# PinkReq.net
KiCad netlist of a schematic drawn in EAGLE
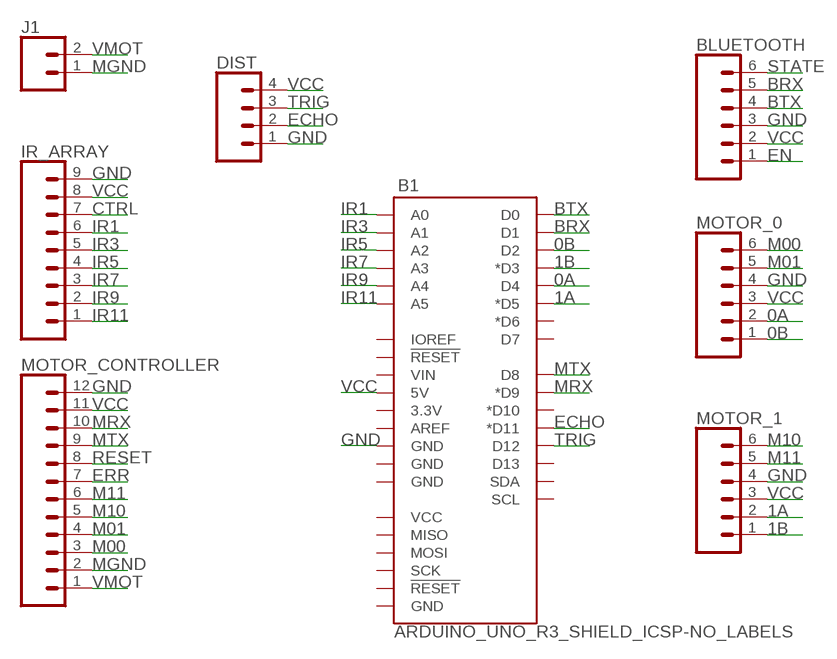
[diagram p0: schematic, sheet 1]

(export (version "E")
  (design (tool "Eeschema 10.0.6"))
  (components
    (comp (ref "B1")
      (value "ARDUINO_UNO_R3_SHIELD_ICSP-NO_LABELS")
      (footprint "eagle-import:UNO_R3_SHIELD_ICSP_NOLABELS")
      (libsource (lib "eagle-import") (part "ARDUINO_UNO_R3_SHIELD_ICSP-NO_LABELS"))
    )
    (comp (ref "BLUETOOTH")
      (value "CONN_06FEMALE_LOCK")
      (footprint "eagle-import:1X06_FEMALE_LOCK.010")
      (libsource (lib "eagle-import") (part "CONN_06FEMALE_LOCK"))
    )
    (comp (ref "DIST")
      (value "CONN_04LOCK")
      (footprint "eagle-import:1X04_LOCK")
      (libsource (lib "eagle-import") (part "CONN_04LOCK"))
    )
    (comp (ref "IR_ARRAY")
      (value "CONN_09LOCK")
      (footprint "eagle-import:1X09_LOCK")
      (libsource (lib "eagle-import") (part "CONN_09LOCK"))
    )
    (comp (ref "J1")
      (value "CONN_025MM")
      (footprint "eagle-import:SCREWTERMINAL-5MM-2")
      (libsource (lib "eagle-import") (part "CONN_025MM"))
    )
    (comp (ref "MOTOR_0")
      (value "CONN_06FEMALE_LOCK")
      (footprint "eagle-import:1X06_FEMALE_LOCK.010")
      (libsource (lib "eagle-import") (part "CONN_06FEMALE_LOCK"))
    )
    (comp (ref "MOTOR_1")
      (value "CONN_06FEMALE_LOCK")
      (footprint "eagle-import:1X06_FEMALE_LOCK.010")
      (libsource (lib "eagle-import") (part "CONN_06FEMALE_LOCK"))
    )
    (comp (ref "MOTOR_CONTROLLER")
      (value "CONN_12LOCK")
      (footprint "eagle-import:1X12_LOCK")
      (libsource (lib "eagle-import") (part "CONN_12LOCK"))
    )
  )
  (nets
    (net (code "1") (name "/0A") (class "Default")
      (node (ref "B1") (pin "D4") (pinfunction "D4_D4") (pintype "bidirectional"))
      (node (ref "MOTOR_0") (pin "2") (pinfunction "2_2") (pintype "passive"))
    )
    (net (code "2") (name "/0B") (class "Default")
      (node (ref "B1") (pin "D2") (pinfunction "D2_D2") (pintype "bidirectional"))
      (node (ref "MOTOR_0") (pin "1") (pinfunction "1_1") (pintype "passive"))
    )
    (net (code "3") (name "/1A") (class "Default")
      (node (ref "B1") (pin "D5") (pinfunction "*D5_D5") (pintype "bidirectional"))
      (node (ref "MOTOR_1") (pin "2") (pinfunction "2_2") (pintype "passive"))
    )
    (net (code "4") (name "/1B") (class "Default")
      (node (ref "B1") (pin "D3") (pinfunction "*D3_D3") (pintype "bidirectional"))
      (node (ref "MOTOR_1") (pin "1") (pinfunction "1_1") (pintype "passive"))
    )
    (net (code "5") (name "/BRX") (class "Default")
      (node (ref "B1") (pin "TX") (pinfunction "D1_TX") (pintype "bidirectional"))
      (node (ref "BLUETOOTH") (pin "5") (pinfunction "5_5") (pintype "passive"))
    )
    (net (code "6") (name "/BTX") (class "Default")
      (node (ref "B1") (pin "RX") (pinfunction "D0_RX") (pintype "bidirectional"))
      (node (ref "BLUETOOTH") (pin "4") (pinfunction "4_4") (pintype "passive"))
    )
    (net (code "7") (name "/CTRL") (class "Default")
      (node (ref "IR_ARRAY") (pin "7") (pinfunction "7_7") (pintype "passive"))
    )
    (net (code "8") (name "/ECHO") (class "Default")
      (node (ref "B1") (pin "D11") (pinfunction "*D11_D11") (pintype "bidirectional"))
      (node (ref "DIST") (pin "2") (pinfunction "2_2") (pintype "passive"))
    )
    (net (code "9") (name "/EN") (class "Default")
      (node (ref "BLUETOOTH") (pin "1") (pinfunction "1_1") (pintype "passive"))
    )
    (net (code "10") (name "/ERR") (class "Default")
      (node (ref "MOTOR_CONTROLLER") (pin "7") (pinfunction "7_7") (pintype "passive"))
    )
    (net (code "11") (name "/GND") (class "Default")
      (node (ref "B1") (pin "GND@2") (pinfunction "GND_GND@2") (pintype "bidirectional"))
      (node (ref "BLUETOOTH") (pin "3") (pinfunction "3_3") (pintype "passive"))
      (node (ref "DIST") (pin "1") (pinfunction "1_1") (pintype "passive"))
      (node (ref "IR_ARRAY") (pin "9") (pinfunction "9_9") (pintype "passive"))
      (node (ref "MOTOR_0") (pin "4") (pinfunction "4_4") (pintype "passive"))
      (node (ref "MOTOR_1") (pin "4") (pinfunction "4_4") (pintype "passive"))
      (node (ref "MOTOR_CONTROLLER") (pin "12") (pinfunction "12_12") (pintype "passive"))
    )
    (net (code "12") (name "/IR1") (class "Default")
      (node (ref "B1") (pin "A0") (pinfunction "A0_A0") (pintype "bidirectional"))
      (node (ref "IR_ARRAY") (pin "6") (pinfunction "6_6") (pintype "passive"))
    )
    (net (code "13") (name "/IR3") (class "Default")
      (node (ref "B1") (pin "A1") (pinfunction "A1_A1") (pintype "bidirectional"))
      (node (ref "IR_ARRAY") (pin "5") (pinfunction "5_5") (pintype "passive"))
    )
    (net (code "14") (name "/IR5") (class "Default")
      (node (ref "B1") (pin "A2") (pinfunction "A2_A2") (pintype "bidirectional"))
      (node (ref "IR_ARRAY") (pin "4") (pinfunction "4_4") (pintype "passive"))
    )
    (net (code "15") (name "/IR7") (class "Default")
      (node (ref "B1") (pin "A3") (pinfunction "A3_A3") (pintype "bidirectional"))
      (node (ref "IR_ARRAY") (pin "3") (pinfunction "3_3") (pintype "passive"))
    )
    (net (code "16") (name "/IR9") (class "Default")
      (node (ref "B1") (pin "A4") (pinfunction "A4_A4") (pintype "bidirectional"))
      (node (ref "IR_ARRAY") (pin "2") (pinfunction "2_2") (pintype "passive"))
    )
    (net (code "17") (name "/IR11") (class "Default")
      (node (ref "B1") (pin "A5") (pinfunction "A5_A5") (pintype "bidirectional"))
      (node (ref "IR_ARRAY") (pin "1") (pinfunction "1_1") (pintype "passive"))
    )
    (net (code "18") (name "/M00") (class "Default")
      (node (ref "MOTOR_0") (pin "6") (pinfunction "6_6") (pintype "passive"))
      (node (ref "MOTOR_CONTROLLER") (pin "3") (pinfunction "3_3") (pintype "passive"))
    )
    (net (code "19") (name "/M01") (class "Default")
      (node (ref "MOTOR_0") (pin "5") (pinfunction "5_5") (pintype "passive"))
      (node (ref "MOTOR_CONTROLLER") (pin "4") (pinfunction "4_4") (pintype "passive"))
    )
    (net (code "20") (name "/M10") (class "Default")
      (node (ref "MOTOR_1") (pin "6") (pinfunction "6_6") (pintype "passive"))
      (node (ref "MOTOR_CONTROLLER") (pin "5") (pinfunction "5_5") (pintype "passive"))
    )
    (net (code "21") (name "/M11") (class "Default")
      (node (ref "MOTOR_1") (pin "5") (pinfunction "5_5") (pintype "passive"))
      (node (ref "MOTOR_CONTROLLER") (pin "6") (pinfunction "6_6") (pintype "passive"))
    )
    (net (code "22") (name "/MGND") (class "Default")
      (node (ref "J1") (pin "1") (pinfunction "1_1") (pintype "passive"))
      (node (ref "MOTOR_CONTROLLER") (pin "2") (pinfunction "2_2") (pintype "passive"))
    )
    (net (code "23") (name "/MRX") (class "Default")
      (node (ref "B1") (pin "D9") (pinfunction "*D9_D9") (pintype "bidirectional"))
      (node (ref "MOTOR_CONTROLLER") (pin "10") (pinfunction "10_10") (pintype "passive"))
    )
    (net (code "24") (name "/MTX") (class "Default")
      (node (ref "B1") (pin "D8") (pinfunction "D8_D8") (pintype "bidirectional"))
      (node (ref "MOTOR_CONTROLLER") (pin "9") (pinfunction "9_9") (pintype "passive"))
    )
    (net (code "25") (name "/RESET") (class "Default")
      (node (ref "MOTOR_CONTROLLER") (pin "8") (pinfunction "8_8") (pintype "passive"))
    )
    (net (code "26") (name "/STATE") (class "Default")
      (node (ref "BLUETOOTH") (pin "6") (pinfunction "6_6") (pintype "passive"))
    )
    (net (code "27") (name "/TRIG") (class "Default")
      (node (ref "B1") (pin "D12") (pinfunction "D12_D12") (pintype "bidirectional"))
      (node (ref "DIST") (pin "3") (pinfunction "3_3") (pintype "passive"))
    )
    (net (code "28") (name "/VCC") (class "Default")
      (node (ref "B1") (pin "5V") (pinfunction "5V_5V") (pintype "bidirectional"))
      (node (ref "BLUETOOTH") (pin "2") (pinfunction "2_2") (pintype "passive"))
      (node (ref "DIST") (pin "4") (pinfunction "4_4") (pintype "passive"))
      (node (ref "IR_ARRAY") (pin "8") (pinfunction "8_8") (pintype "passive"))
      (node (ref "MOTOR_0") (pin "3") (pinfunction "3_3") (pintype "passive"))
      (node (ref "MOTOR_1") (pin "3") (pinfunction "3_3") (pintype "passive"))
      (node (ref "MOTOR_CONTROLLER") (pin "11") (pinfunction "11_11") (pintype "passive"))
    )
    (net (code "29") (name "/VMOT") (class "Default")
      (node (ref "J1") (pin "2") (pinfunction "2_2") (pintype "passive"))
      (node (ref "MOTOR_CONTROLLER") (pin "1") (pinfunction "1_1") (pintype "passive"))
    )
    (net (code "30") (name "unconnected-(B1-*D6-PadD6)") (class "Default")
      (node (ref "B1") (pin "D6") (pinfunction "*D6_D6") (pintype "bidirectional"))
    )
    (net (code "31") (name "unconnected-(B1-*D10-PadD10)") (class "Default")
      (node (ref "B1") (pin "D10") (pinfunction "*D10_D10") (pintype "bidirectional"))
    )
    (net (code "32") (name "unconnected-(B1-GND-PadGND@0)") (class "Default")
      (node (ref "B1") (pin "GND@0") (pinfunction "GND_GND@0") (pintype "bidirectional"))
    )
    (net (code "33") (name "unconnected-(B1-GND-PadGND@1)") (class "Default")
      (node (ref "B1") (pin "GND@1") (pinfunction "GND_GND@1") (pintype "bidirectional"))
    )
    (net (code "34") (name "unconnected-(B1-GND-PadGND_ICSP)") (class "Default")
      (node (ref "B1") (pin "GND_ICSP") (pinfunction "GND_GND_ICSP") (pintype "bidirectional"))
    )
    (net (code "35") (name "unconnected-(B1-Pad3.3V)") (class "Default")
      (node (ref "B1") (pin "3.3V") (pinfunction "3.3V_3.3V") (pintype "bidirectional"))
    )
    (net (code "36") (name "unconnected-(B1-PadAREF)") (class "Default")
      (node (ref "B1") (pin "AREF") (pinfunction "AREF_AREF") (pintype "bidirectional"))
    )
    (net (code "37") (name "unconnected-(B1-PadD7)") (class "Default")
      (node (ref "B1") (pin "D7") (pinfunction "D7_D7") (pintype "bidirectional"))
    )
    (net (code "38") (name "unconnected-(B1-PadD13)") (class "Default")
      (node (ref "B1") (pin "D13") (pinfunction "D13_D13") (pintype "bidirectional"))
    )
    (net (code "39") (name "unconnected-(B1-PadIOREF)") (class "Default")
      (node (ref "B1") (pin "IOREF") (pinfunction "IOREF_IOREF") (pintype "bidirectional"))
    )
    (net (code "40") (name "unconnected-(B1-PadMISO)") (class "Default")
      (node (ref "B1") (pin "MISO") (pinfunction "MISO_MISO") (pintype "bidirectional"))
    )
    (net (code "41") (name "unconnected-(B1-PadMOSI)") (class "Default")
      (node (ref "B1") (pin "MOSI") (pinfunction "MOSI_MOSI") (pintype "bidirectional"))
    )
    (net (code "42") (name "unconnected-(B1-PadSCK)") (class "Default")
      (node (ref "B1") (pin "SCK") (pinfunction "SCK_SCK") (pintype "bidirectional"))
    )
    (net (code "43") (name "unconnected-(B1-PadSCL)") (class "Default")
      (node (ref "B1") (pin "SCL") (pinfunction "SCL_SCL") (pintype "bidirectional"))
    )
    (net (code "44") (name "unconnected-(B1-PadSDA)") (class "Default")
      (node (ref "B1") (pin "SDA") (pinfunction "SDA_SDA") (pintype "bidirectional"))
    )
    (net (code "45") (name "unconnected-(B1-PadVIN)") (class "Default")
      (node (ref "B1") (pin "VIN") (pinfunction "VIN_VIN") (pintype "bidirectional"))
    )
    (net (code "46") (name "unconnected-(B1-VCC-Pad5V_ICSP)") (class "Default")
      (node (ref "B1") (pin "5V_ICSP") (pinfunction "VCC_5V_ICSP") (pintype "bidirectional"))
    )
    (net (code "47") (name "unconnected-(B1-~{RESET}-PadRES)") (class "Default")
      (node (ref "B1") (pin "RES") (pinfunction "~{RESET}_RES") (pintype "bidirectional"))
    )
    (net (code "48") (name "unconnected-(B1-~{RESET}-PadRST_ICSP)") (class "Default")
      (node (ref "B1") (pin "RST_ICSP") (pinfunction "~{RESET}_RST_ICSP") (pintype "bidirectional"))
    )
  )
)
